# Main.net
KiCad netlist of a schematic drawn in EAGLE
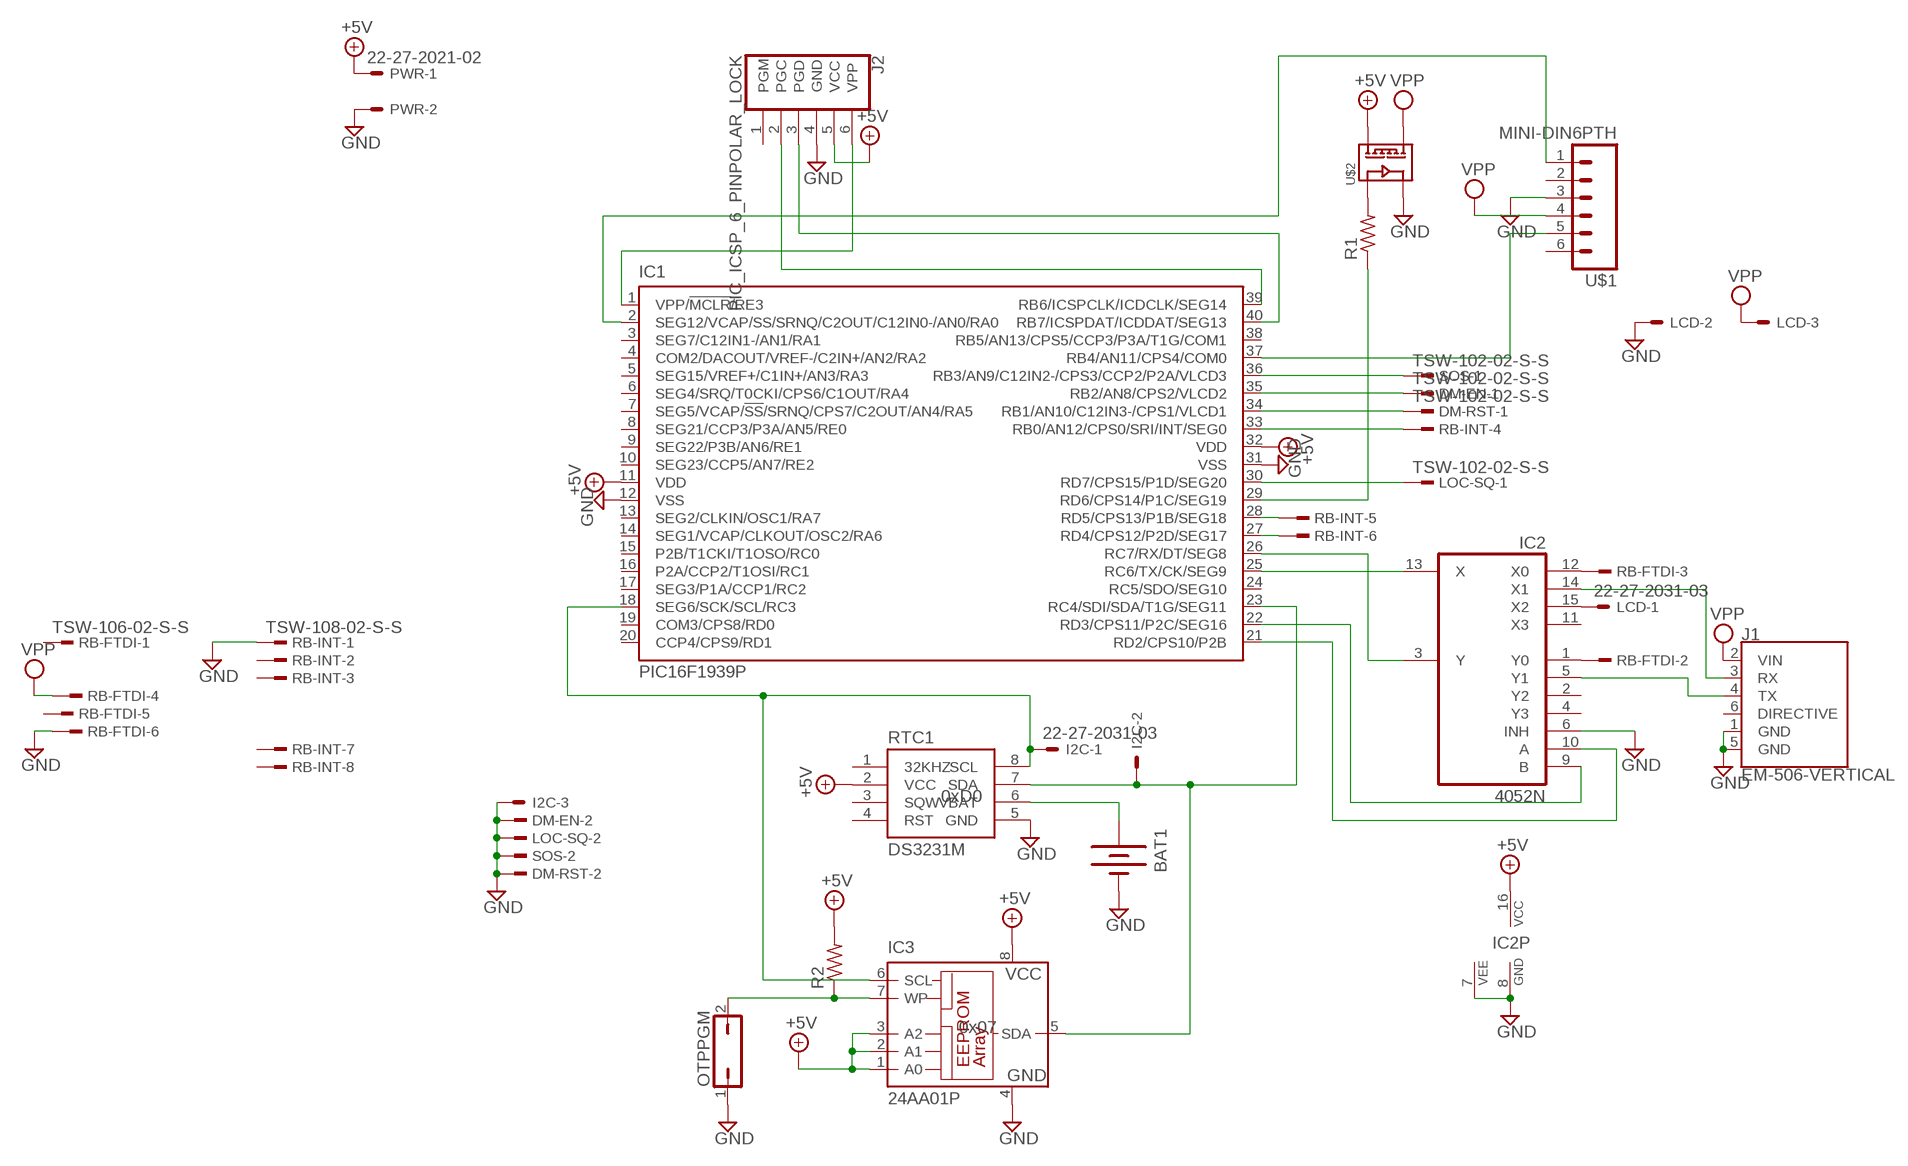
[diagram p0: schematic, sheet 1]

(export (version "E")
  (design (tool "Eeschema 10.0.6"))
  (components
    (comp (ref "BAT1")
      (value "BATTERY12PTH")
      (footprint "eagle-import:BATTCON_12MM_PTH")
      (libsource (lib "eagle-import") (part "BATTERY12PTH"))
    )
    (comp (ref "DM-EN")
      (value "TSW-102-02-S-S")
      (footprint "eagle-import:TSW-102-02-S-S")
      (libsource (lib "eagle-import") (part "TSW-102-02-S-S"))
    )
    (comp (ref "DM-RST")
      (value "TSW-102-02-S-S")
      (footprint "eagle-import:TSW-102-02-S-S")
      (libsource (lib "eagle-import") (part "TSW-102-02-S-S"))
    )
    (comp (ref "I2C")
      (value "22-27-2031-03")
      (footprint "eagle-import:6410-03")
      (libsource (lib "eagle-import") (part "22-?-0327-2031"))
    )
    (comp (ref "IC1")
      (value "PIC16F1939P")
      (footprint "eagle-import:DIL40")
      (fields (field (name "MPN") "PIC16F1939-I/P"))
      (libsource (lib "eagle-import") (part "PIC16F193?P9"))
    )
    (comp (ref "IC2")
      (value "4052N")
      (footprint "eagle-import:DIL16")
      (libsource (lib "eagle-import") (part "4052N"))
    )
    (comp (ref "IC3")
      (value "24AA01P")
      (footprint "eagle-import:DIL8")
      (fields (field (name "MPN") "24AA01-I/P") (field (name "I2CADDR") "0x07"))
      (libsource (lib "eagle-import") (part "24PAA01"))
    )
    (comp (ref "J1")
      (value "EM-506-VERTICAL")
      (footprint "eagle-import:EM406")
      (libsource (lib "eagle-import") (part "EM-506-VERTICAL"))
    )
    (comp (ref "J2")
      (value "PIC_ICSP_6_PINPOLAR_LOCK")
      (footprint "eagle-import:MOLEX-1X6_LOCK")
      (libsource (lib "eagle-import") (part "PIC_ICSP_6_PINPOLAR_LOCK"))
    )
    (comp (ref "LCD")
      (value "22-27-2031-03")
      (footprint "eagle-import:6410-03")
      (libsource (lib "eagle-import") (part "22-?-0327-2031"))
    )
    (comp (ref "LOC-SQ")
      (value "TSW-102-02-S-S")
      (footprint "eagle-import:TSW-102-02-S-S")
      (libsource (lib "eagle-import") (part "TSW-102-02-S-S"))
    )
    (comp (ref "OTPPGM")
      (value "JP1Q")
      (footprint "eagle-import:JP1")
      (libsource (lib "eagle-import") (part "JP1Q"))
    )
    (comp (ref "PWR")
      (value "22-27-2021-02")
      (footprint "eagle-import:6410-02")
      (libsource (lib "eagle-import") (part "22-?-0227-2021"))
    )
    (comp (ref "R1")
      (value "R-US_0204/2V")
      (footprint "eagle-import:0204V")
      (libsource (lib "eagle-import") (part "R-US_0204/2V"))
    )
    (comp (ref "R2")
      (value "R-US_0204/2V")
      (footprint "eagle-import:0204V")
      (libsource (lib "eagle-import") (part "R-US_0204/2V"))
    )
    (comp (ref "RB-FTDI")
      (value "TSW-106-02-S-S")
      (footprint "eagle-import:TSW-106-02-S-S")
      (libsource (lib "eagle-import") (part "TSW-106-02-S-S"))
    )
    (comp (ref "RB-INT")
      (value "TSW-108-02-S-S")
      (footprint "eagle-import:TSW-108-02-S-S")
      (libsource (lib "eagle-import") (part "TSW-108-02-S-S"))
    )
    (comp (ref "RTC1")
      (value "DS3231M")
      (footprint "eagle-import:SOIC8")
      (fields (field (name "I2CADDR") "0xD0"))
      (libsource (lib "eagle-import") (part "DS3231M"))
    )
    (comp (ref "SOS")
      (value "TSW-102-02-S-S")
      (footprint "eagle-import:TSW-102-02-S-S")
      (libsource (lib "eagle-import") (part "TSW-102-02-S-S"))
    )
    (comp (ref "U$1")
      (value "MINI-DIN6PTH")
      (footprint "eagle-import:MINI-DIN6")
      (libsource (lib "eagle-import") (part "MINI-DIN6PTH"))
    )
    (comp (ref "U$2")
      (value "CPC1008N")
      (footprint "eagle-import:SOP04")
      (libsource (lib "eagle-import") (part "CPC1008N"))
    )
  )
  (nets
    (net (code "1") (name "+5V") (class "Default")
      (node (ref "IC1") (pin "11") (pinfunction "VDD_11") (pintype "power_in"))
      (node (ref "IC1") (pin "32") (pinfunction "VDD_32") (pintype "power_in"))
      (node (ref "IC2") (pin "16") (pinfunction "VCC_16") (pintype "power_in"))
      (node (ref "IC3") (pin "1") (pinfunction "A0_1") (pintype "input"))
      (node (ref "IC3") (pin "2") (pinfunction "A1_2") (pintype "input"))
      (node (ref "IC3") (pin "3") (pinfunction "A2_3") (pintype "input"))
      (node (ref "IC3") (pin "8") (pinfunction "VCC_8") (pintype "power_in"))
      (node (ref "J2") (pin "5") (pinfunction "VCC_5") (pintype "power_in"))
      (node (ref "PWR") (pin "1") (pinfunction "S_1") (pintype "passive"))
      (node (ref "R2") (pin "2") (pinfunction "2_2") (pintype "passive"))
      (node (ref "RTC1") (pin "2") (pinfunction "VCC_2") (pintype "power_in"))
      (node (ref "U$2") (pin "4") (pinfunction "DC_4") (pintype "bidirectional"))
    )
    (net (code "2") (name "GND") (class "Default")
      (node (ref "BAT1") (pin "GND") (pinfunction "-_GND") (pintype "power_in"))
      (node (ref "DM-EN") (pin "2") (pinfunction "1_2") (pintype "passive"))
      (node (ref "DM-RST") (pin "2") (pinfunction "1_2") (pintype "passive"))
      (node (ref "I2C") (pin "3") (pinfunction "S_3") (pintype "passive"))
      (node (ref "IC1") (pin "12") (pinfunction "VSS_12") (pintype "power_in"))
      (node (ref "IC1") (pin "31") (pinfunction "VSS_31") (pintype "power_in"))
      (node (ref "IC2") (pin "6") (pinfunction "INH_6") (pintype "input"))
      (node (ref "IC2") (pin "7") (pinfunction "VEE_7") (pintype "power_in"))
      (node (ref "IC2") (pin "8") (pinfunction "GND_8") (pintype "power_in"))
      (node (ref "IC3") (pin "4") (pinfunction "GND_4") (pintype "power_in"))
      (node (ref "J1") (pin "1") (pinfunction "GND_1") (pintype "bidirectional"))
      (node (ref "J1") (pin "5") (pinfunction "GND_5") (pintype "bidirectional"))
      (node (ref "J2") (pin "4") (pinfunction "GND_4") (pintype "power_in"))
      (node (ref "LCD") (pin "2") (pinfunction "S_2") (pintype "passive"))
      (node (ref "LOC-SQ") (pin "2") (pinfunction "1_2") (pintype "passive"))
      (node (ref "OTPPGM") (pin "1") (pinfunction "1_1") (pintype "passive"))
      (node (ref "PWR") (pin "2") (pinfunction "S_2") (pintype "passive"))
      (node (ref "RB-FTDI") (pin "6") (pinfunction "1_6") (pintype "passive"))
      (node (ref "RB-INT") (pin "1") (pinfunction "1_1") (pintype "passive"))
      (node (ref "RTC1") (pin "5") (pinfunction "GND_5") (pintype "power_in"))
      (node (ref "SOS") (pin "2") (pinfunction "1_2") (pintype "passive"))
      (node (ref "U$1") (pin "3") (pinfunction "3_3") (pintype "passive"))
      (node (ref "U$2") (pin "3") (pinfunction "IN-_3") (pintype "power_in"))
    )
    (net (code "3") (name "Net-(BAT1-+)") (class "Default")
      (node (ref "BAT1") (pin "VCC@1") (pinfunction "+_VCC@1") (pintype "power_in"))
      (node (ref "RTC1") (pin "6") (pinfunction "VBAT_6") (pintype "power_in"))
    )
    (net (code "4") (name "Net-(I2CA-S)") (class "Default")
      (node (ref "I2C") (pin "1") (pinfunction "S_1") (pintype "passive"))
      (node (ref "IC1") (pin "18") (pinfunction "SEG6/SCK/SCL/RC3_18") (pintype "bidirectional"))
      (node (ref "IC3") (pin "6") (pinfunction "SCL_6") (pintype "input"))
      (node (ref "RTC1") (pin "8") (pinfunction "SCL_8") (pintype "bidirectional"))
    )
    (net (code "5") (name "Net-(I2CB-S)") (class "Default")
      (node (ref "I2C") (pin "2") (pinfunction "S_2") (pintype "passive"))
      (node (ref "IC1") (pin "23") (pinfunction "RC4/SDI/SDA/T1G/SEG11_23") (pintype "bidirectional"))
      (node (ref "IC3") (pin "5") (pinfunction "SDA_5") (pintype "bidirectional"))
      (node (ref "RTC1") (pin "7") (pinfunction "SDA_7") (pintype "bidirectional"))
    )
    (net (code "6") (name "Net-(IC1-RB0{slash}AN12{slash}CPS0{slash}SRI{slash}INT{slash}SEG0)") (class "Default")
      (node (ref "IC1") (pin "33") (pinfunction "RB0/AN12/CPS0/SRI/INT/SEG0_33") (pintype "bidirectional"))
      (node (ref "RB-INT") (pin "4") (pinfunction "1_4") (pintype "passive"))
    )
    (net (code "7") (name "Net-(IC1-RB1{slash}AN10{slash}C12IN3-{slash}CPS1{slash}VLCD1)") (class "Default")
      (node (ref "DM-RST") (pin "1") (pinfunction "1_1") (pintype "passive"))
      (node (ref "IC1") (pin "34") (pinfunction "RB1/AN10/C12IN3-/CPS1/VLCD1_34") (pintype "bidirectional"))
    )
    (net (code "8") (name "Net-(IC1-RB2{slash}AN8{slash}CPS2{slash}VLCD2)") (class "Default")
      (node (ref "DM-EN") (pin "1") (pinfunction "1_1") (pintype "passive"))
      (node (ref "IC1") (pin "35") (pinfunction "RB2/AN8/CPS2/VLCD2_35") (pintype "bidirectional"))
    )
    (net (code "9") (name "Net-(IC1-RB3{slash}AN9{slash}C12IN2-{slash}CPS3{slash}CCP2{slash}P2A{slash}VLCD3)") (class "Default")
      (node (ref "IC1") (pin "36") (pinfunction "RB3/AN9/C12IN2-/CPS3/CCP2/P2A/VLCD3_36") (pintype "bidirectional"))
      (node (ref "SOS") (pin "1") (pinfunction "1_1") (pintype "passive"))
    )
    (net (code "10") (name "Net-(IC1-RB4{slash}AN11{slash}CPS4{slash}COM0)") (class "Default")
      (node (ref "IC1") (pin "37") (pinfunction "RB4/AN11/CPS4/COM0_37") (pintype "bidirectional"))
      (node (ref "U$1") (pin "5") (pinfunction "5_5") (pintype "passive"))
    )
    (net (code "11") (name "Net-(IC1-RB6{slash}ICSPCLK{slash}ICDCLK{slash}SEG14)") (class "Default")
      (node (ref "IC1") (pin "39") (pinfunction "RB6/ICSPCLK/ICDCLK/SEG14_39") (pintype "bidirectional"))
      (node (ref "J2") (pin "2") (pinfunction "PGC_2") (pintype "bidirectional"))
    )
    (net (code "12") (name "Net-(IC1-RB7{slash}ICSPDAT{slash}ICDDAT{slash}SEG13)") (class "Default")
      (node (ref "IC1") (pin "40") (pinfunction "RB7/ICSPDAT/ICDDAT/SEG13_40") (pintype "bidirectional"))
      (node (ref "J2") (pin "3") (pinfunction "PGD_3") (pintype "bidirectional"))
    )
    (net (code "13") (name "Net-(IC1-RC6{slash}TX{slash}CK{slash}SEG9)") (class "Default")
      (node (ref "IC1") (pin "25") (pinfunction "RC6/TX/CK/SEG9_25") (pintype "bidirectional"))
      (node (ref "IC2") (pin "13") (pinfunction "X_13") (pintype "bidirectional"))
    )
    (net (code "14") (name "Net-(IC1-RC7{slash}RX{slash}DT{slash}SEG8)") (class "Default")
      (node (ref "IC1") (pin "26") (pinfunction "RC7/RX/DT/SEG8_26") (pintype "bidirectional"))
      (node (ref "IC2") (pin "3") (pinfunction "Y_3") (pintype "bidirectional"))
    )
    (net (code "15") (name "Net-(IC1-RD2{slash}CPS10{slash}P2B)") (class "Default")
      (node (ref "IC1") (pin "21") (pinfunction "RD2/CPS10/P2B_21") (pintype "bidirectional"))
      (node (ref "IC2") (pin "10") (pinfunction "A_10") (pintype "input"))
    )
    (net (code "16") (name "Net-(IC1-RD3{slash}CPS11{slash}P2C{slash}SEG16)") (class "Default")
      (node (ref "IC1") (pin "22") (pinfunction "RD3/CPS11/P2C/SEG16_22") (pintype "bidirectional"))
      (node (ref "IC2") (pin "9") (pinfunction "B_9") (pintype "input"))
    )
    (net (code "17") (name "Net-(IC1-RD4{slash}CPS12{slash}P2D{slash}SEG17)") (class "Default")
      (node (ref "IC1") (pin "27") (pinfunction "RD4/CPS12/P2D/SEG17_27") (pintype "bidirectional"))
      (node (ref "RB-INT") (pin "6") (pinfunction "1_6") (pintype "passive"))
    )
    (net (code "18") (name "Net-(IC1-RD5{slash}CPS13{slash}P1B{slash}SEG18)") (class "Default")
      (node (ref "IC1") (pin "28") (pinfunction "RD5/CPS13/P1B/SEG18_28") (pintype "bidirectional"))
      (node (ref "RB-INT") (pin "5") (pinfunction "1_5") (pintype "passive"))
    )
    (net (code "19") (name "Net-(IC1-RD6{slash}CPS14{slash}P1C{slash}SEG19)") (class "Default")
      (node (ref "IC1") (pin "29") (pinfunction "RD6/CPS14/P1C/SEG19_29") (pintype "bidirectional"))
      (node (ref "R1") (pin "1") (pinfunction "1_1") (pintype "passive"))
    )
    (net (code "20") (name "Net-(IC1-RD7{slash}CPS15{slash}P1D{slash}SEG20)") (class "Default")
      (node (ref "IC1") (pin "30") (pinfunction "RD7/CPS15/P1D/SEG20_30") (pintype "bidirectional"))
      (node (ref "LOC-SQ") (pin "1") (pinfunction "1_1") (pintype "passive"))
    )
    (net (code "21") (name "Net-(IC1-SEG12{slash}VCAP{slash}SS{slash}SRNQ{slash}C2OUT{slash}C12IN0-{slash}AN0{slash}RA0)") (class "Default")
      (node (ref "IC1") (pin "2") (pinfunction "SEG12/VCAP/SS/SRNQ/C2OUT/C12IN0-/AN0/RA0_2") (pintype "bidirectional"))
      (node (ref "U$1") (pin "1") (pinfunction "1_1") (pintype "passive"))
    )
    (net (code "22") (name "Net-(IC1-VPP{slash}~{MCLR}{slash}RE3)") (class "Default")
      (node (ref "IC1") (pin "1") (pinfunction "VPP/~{MCLR}/RE3_1") (pintype "input"))
      (node (ref "J2") (pin "6") (pinfunction "VPP_6") (pintype "bidirectional"))
    )
    (net (code "23") (name "Net-(IC2A-X0)") (class "Default")
      (node (ref "IC2") (pin "12") (pinfunction "X0_12") (pintype "bidirectional"))
      (node (ref "RB-FTDI") (pin "3") (pinfunction "1_3") (pintype "passive"))
    )
    (net (code "24") (name "Net-(IC2A-X1)") (class "Default")
      (node (ref "IC2") (pin "14") (pinfunction "X1_14") (pintype "bidirectional"))
      (node (ref "J1") (pin "3") (pinfunction "RX_3") (pintype "bidirectional"))
    )
    (net (code "25") (name "Net-(IC2A-X2)") (class "Default")
      (node (ref "IC2") (pin "15") (pinfunction "X2_15") (pintype "bidirectional"))
      (node (ref "LCD") (pin "1") (pinfunction "S_1") (pintype "passive"))
    )
    (net (code "26") (name "Net-(IC2A-Y0)") (class "Default")
      (node (ref "IC2") (pin "1") (pinfunction "Y0_1") (pintype "bidirectional"))
      (node (ref "RB-FTDI") (pin "2") (pinfunction "1_2") (pintype "passive"))
    )
    (net (code "27") (name "Net-(IC2A-Y1)") (class "Default")
      (node (ref "IC2") (pin "5") (pinfunction "Y1_5") (pintype "bidirectional"))
      (node (ref "J1") (pin "4") (pinfunction "TX_4") (pintype "bidirectional"))
    )
    (net (code "28") (name "Net-(IC3-WP)") (class "Default")
      (node (ref "IC3") (pin "7") (pinfunction "WP_7") (pintype "input"))
      (node (ref "OTPPGM") (pin "2") (pinfunction "2_2") (pintype "passive"))
      (node (ref "R2") (pin "1") (pinfunction "1_1") (pintype "passive"))
    )
    (net (code "29") (name "Net-(U$2-IN+)") (class "Default")
      (node (ref "R1") (pin "2") (pinfunction "2_2") (pintype "passive"))
      (node (ref "U$2") (pin "1") (pinfunction "IN+_1") (pintype "input"))
    )
    (net (code "30") (name "VPP") (class "Default")
      (node (ref "J1") (pin "2") (pinfunction "VIN_2") (pintype "bidirectional"))
      (node (ref "LCD") (pin "3") (pinfunction "S_3") (pintype "passive"))
      (node (ref "RB-FTDI") (pin "4") (pinfunction "1_4") (pintype "passive"))
      (node (ref "U$1") (pin "4") (pinfunction "4_4") (pintype "passive"))
      (node (ref "U$2") (pin "6") (pinfunction "DC_6") (pintype "bidirectional"))
    )
    (net (code "31") (name "unconnected-(IC1-CCP4{slash}CPS9{slash}RD1-Pad20)") (class "Default")
      (node (ref "IC1") (pin "20") (pinfunction "CCP4/CPS9/RD1_20") (pintype "bidirectional"))
    )
    (net (code "32") (name "unconnected-(IC1-COM2{slash}DACOUT{slash}VREF-{slash}C2IN+{slash}AN2{slash}RA2-Pad4)") (class "Default")
      (node (ref "IC1") (pin "4") (pinfunction "COM2/DACOUT/VREF-/C2IN+/AN2/RA2_4") (pintype "bidirectional"))
    )
    (net (code "33") (name "unconnected-(IC1-COM3{slash}CPS8{slash}RD0-Pad19)") (class "Default")
      (node (ref "IC1") (pin "19") (pinfunction "COM3/CPS8/RD0_19") (pintype "bidirectional"))
    )
    (net (code "34") (name "unconnected-(IC1-P2A{slash}CCP2{slash}T1OSI{slash}RC1-Pad16)") (class "Default")
      (node (ref "IC1") (pin "16") (pinfunction "P2A/CCP2/T1OSI/RC1_16") (pintype "bidirectional"))
    )
    (net (code "35") (name "unconnected-(IC1-P2B{slash}T1CKI{slash}T1OSO{slash}RC0-Pad15)") (class "Default")
      (node (ref "IC1") (pin "15") (pinfunction "P2B/T1CKI/T1OSO/RC0_15") (pintype "bidirectional"))
    )
    (net (code "36") (name "unconnected-(IC1-RB5{slash}AN13{slash}CPS5{slash}CCP3{slash}P3A{slash}T1G{slash}COM1-Pad38)") (class "Default")
      (node (ref "IC1") (pin "38") (pinfunction "RB5/AN13/CPS5/CCP3/P3A/T1G/COM1_38") (pintype "bidirectional"))
    )
    (net (code "37") (name "unconnected-(IC1-RC5{slash}SDO{slash}SEG10-Pad24)") (class "Default")
      (node (ref "IC1") (pin "24") (pinfunction "RC5/SDO/SEG10_24") (pintype "bidirectional"))
    )
    (net (code "38") (name "unconnected-(IC1-SEG1{slash}VCAP{slash}CLKOUT{slash}OSC2{slash}RA6-Pad14)") (class "Default")
      (node (ref "IC1") (pin "14") (pinfunction "SEG1/VCAP/CLKOUT/OSC2/RA6_14") (pintype "bidirectional"))
    )
    (net (code "39") (name "unconnected-(IC1-SEG2{slash}CLKIN{slash}OSC1{slash}RA7-Pad13)") (class "Default")
      (node (ref "IC1") (pin "13") (pinfunction "SEG2/CLKIN/OSC1/RA7_13") (pintype "bidirectional"))
    )
    (net (code "40") (name "unconnected-(IC1-SEG3{slash}P1A{slash}CCP1{slash}RC2-Pad17)") (class "Default")
      (node (ref "IC1") (pin "17") (pinfunction "SEG3/P1A/CCP1/RC2_17") (pintype "bidirectional"))
    )
    (net (code "41") (name "unconnected-(IC1-SEG4{slash}SRQ{slash}T0CKI{slash}CPS6{slash}C1OUT{slash}RA4-Pad6)") (class "Default")
      (node (ref "IC1") (pin "6") (pinfunction "SEG4/SRQ/T0CKI/CPS6/C1OUT/RA4_6") (pintype "bidirectional"))
    )
    (net (code "42") (name "unconnected-(IC1-SEG5{slash}VCAP{slash}~{SS}{slash}SRNQ{slash}CPS7{slash}C2OUT{slash}AN4{slash}RA5-Pad7)") (class "Default")
      (node (ref "IC1") (pin "7") (pinfunction "SEG5/VCAP/~{SS}/SRNQ/CPS7/C2OUT/AN4/RA5_7") (pintype "bidirectional"))
    )
    (net (code "43") (name "unconnected-(IC1-SEG7{slash}C12IN1-{slash}AN1{slash}RA1-Pad3)") (class "Default")
      (node (ref "IC1") (pin "3") (pinfunction "SEG7/C12IN1-/AN1/RA1_3") (pintype "bidirectional"))
    )
    (net (code "44") (name "unconnected-(IC1-SEG15{slash}VREF+{slash}C1IN+{slash}AN3{slash}RA3-Pad5)") (class "Default")
      (node (ref "IC1") (pin "5") (pinfunction "SEG15/VREF+/C1IN+/AN3/RA3_5") (pintype "bidirectional"))
    )
    (net (code "45") (name "unconnected-(IC1-SEG21{slash}CCP3{slash}P3A{slash}AN5{slash}RE0-Pad8)") (class "Default")
      (node (ref "IC1") (pin "8") (pinfunction "SEG21/CCP3/P3A/AN5/RE0_8") (pintype "bidirectional"))
    )
    (net (code "46") (name "unconnected-(IC1-SEG22{slash}P3B{slash}AN6{slash}RE1-Pad9)") (class "Default")
      (node (ref "IC1") (pin "9") (pinfunction "SEG22/P3B/AN6/RE1_9") (pintype "bidirectional"))
    )
    (net (code "47") (name "unconnected-(IC1-SEG23{slash}CCP5{slash}AN7{slash}RE2-Pad10)") (class "Default")
      (node (ref "IC1") (pin "10") (pinfunction "SEG23/CCP5/AN7/RE2_10") (pintype "bidirectional"))
    )
    (net (code "48") (name "unconnected-(IC2A-X3-Pad11)") (class "Default")
      (node (ref "IC2") (pin "11") (pinfunction "X3_11") (pintype "bidirectional"))
    )
    (net (code "49") (name "unconnected-(IC2A-Y2-Pad2)") (class "Default")
      (node (ref "IC2") (pin "2") (pinfunction "Y2_2") (pintype "bidirectional"))
    )
    (net (code "50") (name "unconnected-(IC2A-Y3-Pad4)") (class "Default")
      (node (ref "IC2") (pin "4") (pinfunction "Y3_4") (pintype "bidirectional"))
    )
    (net (code "51") (name "unconnected-(J1-DIRECTIVE-Pad6)") (class "Default")
      (node (ref "J1") (pin "6") (pinfunction "DIRECTIVE_6") (pintype "bidirectional"))
    )
    (net (code "52") (name "unconnected-(J2-PGM-Pad1)") (class "Default")
      (node (ref "J2") (pin "1") (pinfunction "PGM_1") (pintype "bidirectional"))
    )
    (net (code "53") (name "unconnected-(RB-FTDI-Pad1)") (class "Default")
      (node (ref "RB-FTDI") (pin "1") (pinfunction "1_1") (pintype "passive"))
    )
    (net (code "54") (name "unconnected-(RB-FTDIE-1-Pad5)") (class "Default")
      (node (ref "RB-FTDI") (pin "5") (pinfunction "1_5") (pintype "passive"))
    )
    (net (code "55") (name "unconnected-(RB-INTB-1-Pad2)") (class "Default")
      (node (ref "RB-INT") (pin "2") (pinfunction "1_2") (pintype "passive"))
    )
    (net (code "56") (name "unconnected-(RB-INTC-1-Pad3)") (class "Default")
      (node (ref "RB-INT") (pin "3") (pinfunction "1_3") (pintype "passive"))
    )
    (net (code "57") (name "unconnected-(RB-INTG-1-Pad7)") (class "Default")
      (node (ref "RB-INT") (pin "7") (pinfunction "1_7") (pintype "passive"))
    )
    (net (code "58") (name "unconnected-(RB-INTH-1-Pad8)") (class "Default")
      (node (ref "RB-INT") (pin "8") (pinfunction "1_8") (pintype "passive"))
    )
    (net (code "59") (name "unconnected-(RTC1-32KHZ-Pad1)") (class "Default")
      (node (ref "RTC1") (pin "1") (pinfunction "32KHZ_1") (pintype "output"))
    )
    (net (code "60") (name "unconnected-(RTC1-RST-Pad4)") (class "Default")
      (node (ref "RTC1") (pin "4") (pinfunction "RST_4") (pintype "bidirectional"))
    )
    (net (code "61") (name "unconnected-(RTC1-SQW-Pad3)") (class "Default")
      (node (ref "RTC1") (pin "3") (pinfunction "SQW_3") (pintype "output"))
    )
    (net (code "62") (name "unconnected-(U$1-Pad2)") (class "Default")
      (node (ref "U$1") (pin "2") (pinfunction "2_2") (pintype "passive"))
    )
    (net (code "63") (name "unconnected-(U$1-Pad6)") (class "Default")
      (node (ref "U$1") (pin "6") (pinfunction "6_6") (pintype "passive"))
    )
  )
)
